# Segment16Keyboard.net
KiCad netlist of a schematic drawn in EAGLE
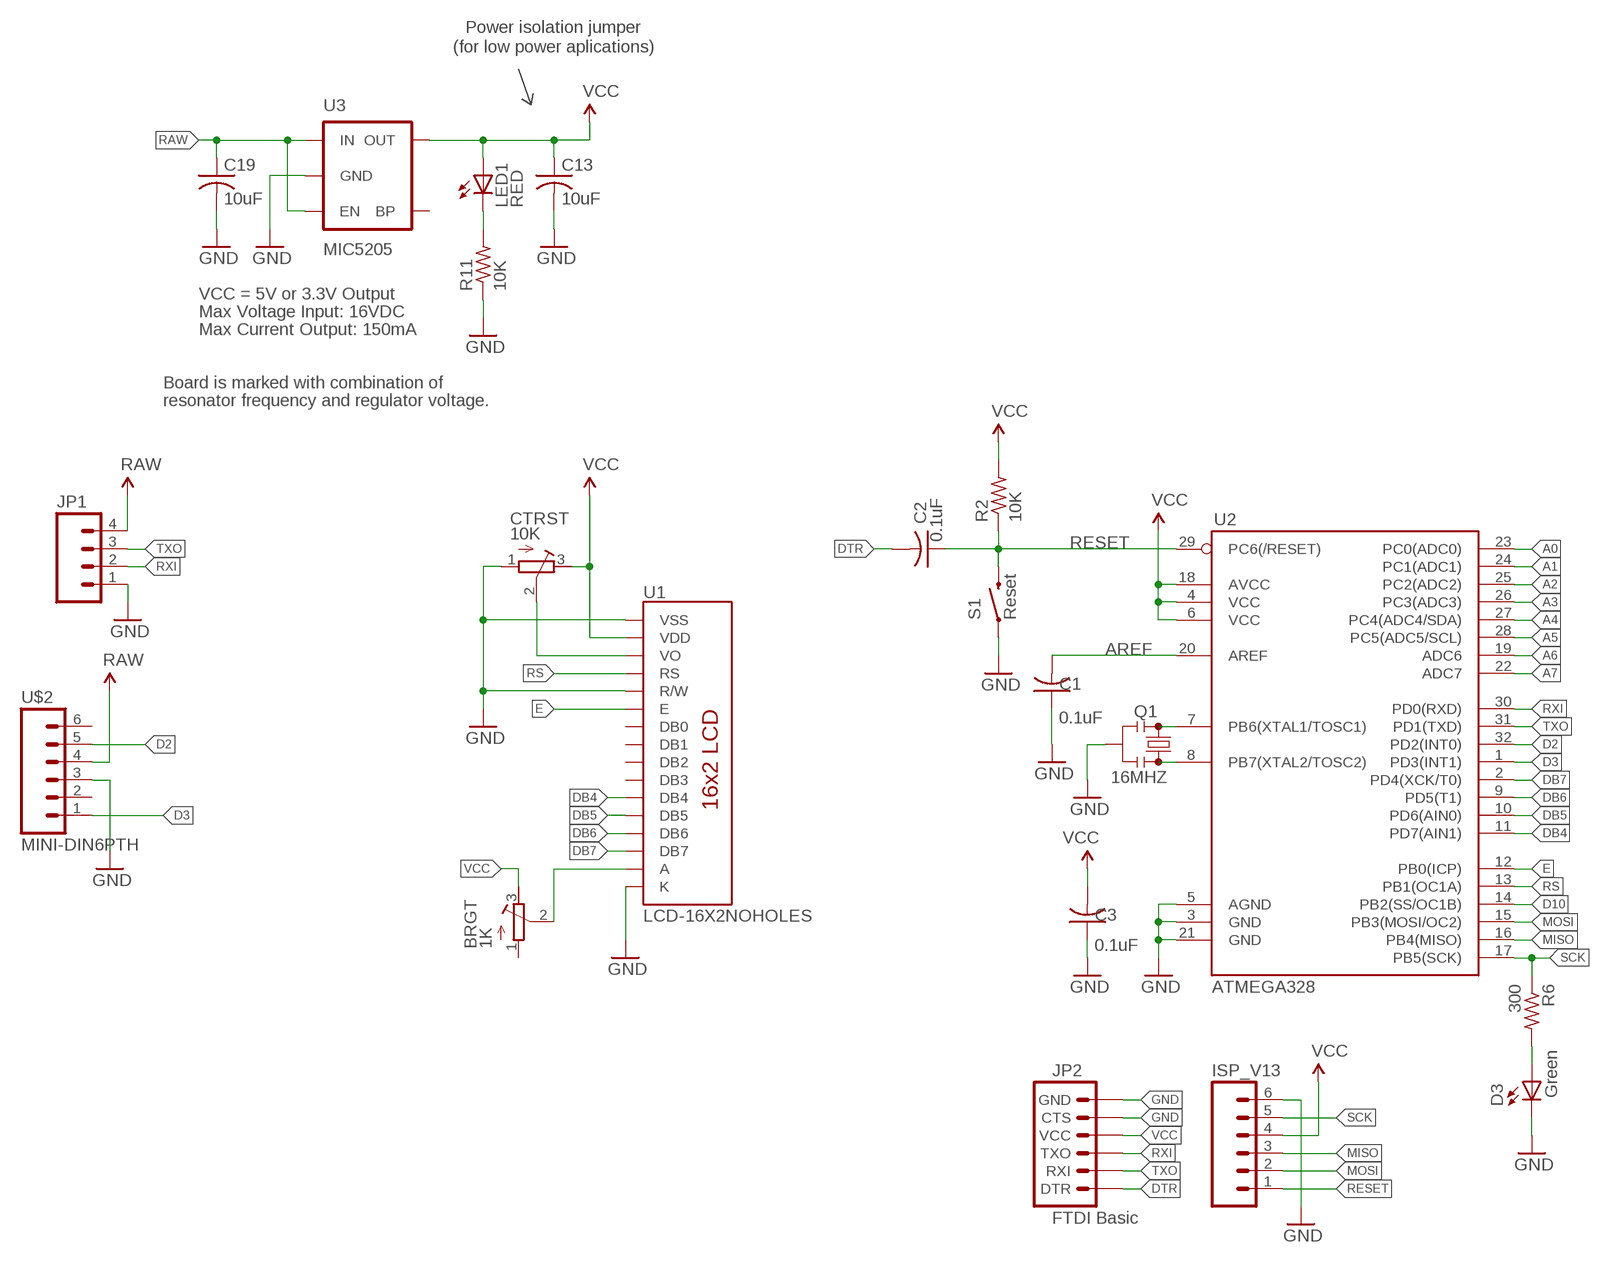
[diagram p0: schematic, sheet 1]

(export (version "E")
  (design (tool "Eeschema 10.0.6"))
  (components
    (comp (ref "BRGT")
      (value "1K")
      (footprint "eagle-import:RTRIM3296W")
      (libsource (lib "eagle-import") (part "R-TRIMM3296W"))
    )
    (comp (ref "C1")
      (value "0.1uF")
      (footprint "eagle-import:C0805")
      (libsource (lib "eagle-import") (part "C-USC0805"))
    )
    (comp (ref "C2")
      (value "0.1uF")
      (footprint "eagle-import:C0805")
      (libsource (lib "eagle-import") (part "C-USC0805"))
    )
    (comp (ref "C3")
      (value "0.1uF")
      (footprint "eagle-import:C0805")
      (libsource (lib "eagle-import") (part "C-USC0805"))
    )
    (comp (ref "C13")
      (value "10uF")
      (footprint "eagle-import:C0805")
      (libsource (lib "eagle-import") (part "resistor_C-USC0805"))
    )
    (comp (ref "C19")
      (value "10uF")
      (footprint "eagle-import:C0805")
      (libsource (lib "eagle-import") (part "resistor_C-USC0805"))
    )
    (comp (ref "CTRST")
      (value "10K")
      (footprint "eagle-import:RTRIM3296W")
      (libsource (lib "eagle-import") (part "R-TRIMM3296W"))
    )
    (comp (ref "D3")
      (value "Green")
      (footprint "eagle-import:CHIPLED_0805")
      (libsource (lib "eagle-import") (part "LEDCHIPLED_0805"))
    )
    (comp (ref "ISP_V13")
      (value "M06SIP")
      (footprint "eagle-import:1X06")
      (libsource (lib "eagle-import") (part "M06SIP"))
    )
    (comp (ref "JP1")
      (value "M041X04_NO_SILK")
      (footprint "eagle-import:1X04_NO_SILK")
      (libsource (lib "eagle-import") (part "M041X04_NO_SILK"))
    )
    (comp (ref "JP2")
      (value "FTDI Basic")
      (footprint "eagle-import:1X06")
      (libsource (lib "eagle-import") (part "ARDUINO_SERIAL_PROGRAMPTH"))
    )
    (comp (ref "LED1")
      (value "RED")
      (footprint "eagle-import:0603-LED-ALT1")
      (libsource (lib "eagle-import") (part "LED"))
    )
    (comp (ref "Q1")
      (value "16MHZ")
      (footprint "eagle-import:RESONATOR-SMD")
      (libsource (lib "eagle-import") (part "RESONATOR16MHZ"))
    )
    (comp (ref "R2")
      (value "10K")
      (footprint "eagle-import:M0805")
      (libsource (lib "eagle-import") (part "R-US_M0805"))
    )
    (comp (ref "R6")
      (value "300")
      (footprint "eagle-import:M0805")
      (libsource (lib "eagle-import") (part "R-US_M0805"))
    )
    (comp (ref "R11")
      (value "10K")
      (footprint "eagle-import:R0805")
      (libsource (lib "eagle-import") (part "R-US_R0805"))
    )
    (comp (ref "S1")
      (value "Reset")
      (footprint "eagle-import:TACTILE-SWITCH-SMD-ALT01")
      (libsource (lib "eagle-import") (part "SWITCH-MOMENTARY-2SMD-ALT01"))
    )
    (comp (ref "U$2")
      (value "MINI-DIN6PTH")
      (footprint "eagle-import:MINI-DIN6")
      (libsource (lib "eagle-import") (part "MINI-DIN6PTH"))
    )
    (comp (ref "U1")
      (value "LCD-16X2NOHOLES")
      (footprint "eagle-import:LCD-16X2_NOHOLES")
      (libsource (lib "eagle-import") (part "LCD-16X2NOHOLES"))
    )
    (comp (ref "U2")
      (value "ATMEGA328")
      (footprint "eagle-import:TQFP32-08")
      (libsource (lib "eagle-import") (part "ATMEGA168"))
    )
    (comp (ref "U3")
      (value "MIC5205")
      (footprint "eagle-import:SOT23-5")
      (libsource (lib "eagle-import") (part "V_REG_LDOSMD"))
    )
  )
  (nets
    (net (code "1") (name "/AREF") (class "Default")
      (node (ref "C1") (pin "2") (pinfunction "2_2") (pintype "passive"))
      (node (ref "U2") (pin "20") (pinfunction "AREF_20") (pintype "bidirectional"))
    )
    (net (code "2") (name "A0") (class "Default")
      (node (ref "U2") (pin "23") (pinfunction "PC0(ADC0)_23") (pintype "bidirectional"))
    )
    (net (code "3") (name "A1") (class "Default")
      (node (ref "U2") (pin "24") (pinfunction "PC1(ADC1)_24") (pintype "bidirectional"))
    )
    (net (code "4") (name "A2") (class "Default")
      (node (ref "U2") (pin "25") (pinfunction "PC2(ADC2)_25") (pintype "bidirectional"))
    )
    (net (code "5") (name "A3") (class "Default")
      (node (ref "U2") (pin "26") (pinfunction "PC3(ADC3)_26") (pintype "bidirectional"))
    )
    (net (code "6") (name "A4") (class "Default")
      (node (ref "U2") (pin "27") (pinfunction "PC4(ADC4/SDA)_27") (pintype "bidirectional"))
    )
    (net (code "7") (name "A5") (class "Default")
      (node (ref "U2") (pin "28") (pinfunction "PC5(ADC5/SCL)_28") (pintype "bidirectional"))
    )
    (net (code "8") (name "A6") (class "Default")
      (node (ref "U2") (pin "19") (pinfunction "ADC6_19") (pintype "bidirectional"))
    )
    (net (code "9") (name "A7") (class "Default")
      (node (ref "U2") (pin "22") (pinfunction "ADC7_22") (pintype "bidirectional"))
    )
    (net (code "10") (name "D2") (class "Default")
      (node (ref "U$2") (pin "5") (pinfunction "5_5") (pintype "passive"))
      (node (ref "U2") (pin "32") (pinfunction "PD2(INT0)_32") (pintype "bidirectional"))
    )
    (net (code "11") (name "D3") (class "Default")
      (node (ref "U$2") (pin "1") (pinfunction "1_1") (pintype "passive"))
      (node (ref "U2") (pin "1") (pinfunction "PD3(INT1)_1") (pintype "bidirectional"))
    )
    (net (code "12") (name "D10") (class "Default")
      (node (ref "U2") (pin "14") (pinfunction "PB2(SS/OC1B)_14") (pintype "bidirectional"))
    )
    (net (code "13") (name "DB4") (class "Default")
      (node (ref "U1") (pin "11") (pinfunction "DB4_11") (pintype "bidirectional"))
      (node (ref "U2") (pin "11") (pinfunction "PD7(AIN1)_11") (pintype "bidirectional"))
    )
    (net (code "14") (name "DB5") (class "Default")
      (node (ref "U1") (pin "12") (pinfunction "DB5_12") (pintype "bidirectional"))
      (node (ref "U2") (pin "10") (pinfunction "PD6(AIN0)_10") (pintype "bidirectional"))
    )
    (net (code "15") (name "DB6") (class "Default")
      (node (ref "U1") (pin "13") (pinfunction "DB6_13") (pintype "bidirectional"))
      (node (ref "U2") (pin "9") (pinfunction "PD5(T1)_9") (pintype "bidirectional"))
    )
    (net (code "16") (name "DB7") (class "Default")
      (node (ref "U1") (pin "14") (pinfunction "DB7_14") (pintype "bidirectional"))
      (node (ref "U2") (pin "2") (pinfunction "PD4(XCK/T0)_2") (pintype "bidirectional"))
    )
    (net (code "17") (name "DTR") (class "Default")
      (node (ref "C2") (pin "2") (pinfunction "2_2") (pintype "passive"))
      (node (ref "JP2") (pin "1") (pinfunction "DTR_1") (pintype "passive"))
    )
    (net (code "18") (name "E") (class "Default")
      (node (ref "U1") (pin "6") (pinfunction "E_6") (pintype "input"))
      (node (ref "U2") (pin "12") (pinfunction "PB0(ICP)_12") (pintype "bidirectional"))
    )
    (net (code "19") (name "GND") (class "Default")
      (node (ref "C1") (pin "1") (pinfunction "1_1") (pintype "passive"))
      (node (ref "C13") (pin "2") (pinfunction "2_2") (pintype "passive"))
      (node (ref "C19") (pin "2") (pinfunction "2_2") (pintype "passive"))
      (node (ref "C3") (pin "1") (pinfunction "1_1") (pintype "passive"))
      (node (ref "CTRST") (pin "1") (pinfunction "A_1") (pintype "passive"))
      (node (ref "D3") (pin "C") (pinfunction "C_C") (pintype "passive"))
      (node (ref "ISP_V13") (pin "6") (pinfunction "6_6") (pintype "passive"))
      (node (ref "JP1") (pin "1") (pinfunction "1_1") (pintype "passive"))
      (node (ref "JP2") (pin "5") (pinfunction "CTS_5") (pintype "passive"))
      (node (ref "JP2") (pin "6") (pinfunction "GND_6") (pintype "passive"))
      (node (ref "Q1") (pin "2") (pinfunction "2_2") (pintype "passive"))
      (node (ref "R11") (pin "1") (pinfunction "1_1") (pintype "passive"))
      (node (ref "S1") (pin "1") (pinfunction "1_1") (pintype "passive"))
      (node (ref "S1") (pin "2") (pinfunction "1_2") (pintype "passive"))
      (node (ref "U$2") (pin "3") (pinfunction "3_3") (pintype "passive"))
      (node (ref "U1") (pin "1") (pinfunction "VSS_1") (pintype "power_in"))
      (node (ref "U1") (pin "16") (pinfunction "K_16") (pintype "power_in"))
      (node (ref "U1") (pin "5") (pinfunction "R/W_5") (pintype "input"))
      (node (ref "U2") (pin "21") (pinfunction "GND_21") (pintype "bidirectional"))
      (node (ref "U2") (pin "3") (pinfunction "GND_3") (pintype "bidirectional"))
      (node (ref "U2") (pin "5") (pinfunction "AGND_5") (pintype "bidirectional"))
      (node (ref "U3") (pin "2") (pinfunction "GND_2") (pintype "input"))
    )
    (net (code "20") (name "MISO") (class "Default")
      (node (ref "ISP_V13") (pin "3") (pinfunction "3_3") (pintype "passive"))
      (node (ref "U2") (pin "16") (pinfunction "PB4(MISO)_16") (pintype "bidirectional"))
    )
    (net (code "21") (name "MOSI") (class "Default")
      (node (ref "ISP_V13") (pin "2") (pinfunction "2_2") (pintype "passive"))
      (node (ref "U2") (pin "15") (pinfunction "PB3(MOSI/OC2)_15") (pintype "bidirectional"))
    )
    (net (code "22") (name "Net-(BRGT-S)") (class "Default")
      (node (ref "BRGT") (pin "2") (pinfunction "S_2") (pintype "passive"))
      (node (ref "U1") (pin "15") (pinfunction "A_15") (pintype "power_in"))
    )
    (net (code "23") (name "Net-(CTRST-S)") (class "Default")
      (node (ref "CTRST") (pin "2") (pinfunction "S_2") (pintype "passive"))
      (node (ref "U1") (pin "3") (pinfunction "VO_3") (pintype "bidirectional"))
    )
    (net (code "24") (name "Net-(D3-PadA)") (class "Default")
      (node (ref "D3") (pin "A") (pinfunction "A_A") (pintype "passive"))
      (node (ref "R6") (pin "2") (pinfunction "2_2") (pintype "passive"))
    )
    (net (code "25") (name "Net-(LED1-PadC)") (class "Default")
      (node (ref "LED1") (pin "C") (pinfunction "C_C") (pintype "passive"))
      (node (ref "R11") (pin "2") (pinfunction "2_2") (pintype "passive"))
    )
    (net (code "26") (name "Net-(U2-PB6(XTAL1{slash}TOSC1))") (class "Default")
      (node (ref "Q1") (pin "1") (pinfunction "1_1") (pintype "passive"))
      (node (ref "U2") (pin "7") (pinfunction "PB6(XTAL1/TOSC1)_7") (pintype "bidirectional"))
    )
    (net (code "27") (name "Net-(U2-PB7(XTAL2{slash}TOSC2))") (class "Default")
      (node (ref "Q1") (pin "3") (pinfunction "3_3") (pintype "passive"))
      (node (ref "U2") (pin "8") (pinfunction "PB7(XTAL2/TOSC2)_8") (pintype "bidirectional"))
    )
    (net (code "28") (name "RAW") (class "Default")
      (node (ref "C19") (pin "1") (pinfunction "1_1") (pintype "passive"))
      (node (ref "JP1") (pin "4") (pinfunction "4_4") (pintype "passive"))
      (node (ref "U$2") (pin "4") (pinfunction "4_4") (pintype "passive"))
      (node (ref "U3") (pin "1") (pinfunction "IN_1") (pintype "input"))
      (node (ref "U3") (pin "3") (pinfunction "EN_3") (pintype "input"))
    )
    (net (code "29") (name "RESET") (class "Default")
      (node (ref "C2") (pin "1") (pinfunction "1_1") (pintype "passive"))
      (node (ref "ISP_V13") (pin "1") (pinfunction "1_1") (pintype "passive"))
      (node (ref "R2") (pin "1") (pinfunction "1_1") (pintype "passive"))
      (node (ref "S1") (pin "3") (pinfunction "2_3") (pintype "passive"))
      (node (ref "S1") (pin "4") (pinfunction "2_4") (pintype "passive"))
      (node (ref "U2") (pin "29") (pinfunction "PC6(/RESET)_29") (pintype "bidirectional"))
    )
    (net (code "30") (name "RS") (class "Default")
      (node (ref "U1") (pin "4") (pinfunction "RS_4") (pintype "input"))
      (node (ref "U2") (pin "13") (pinfunction "PB1(OC1A)_13") (pintype "bidirectional"))
    )
    (net (code "31") (name "RXI") (class "Default")
      (node (ref "JP1") (pin "2") (pinfunction "2_2") (pintype "passive"))
      (node (ref "JP2") (pin "3") (pinfunction "TXO_3") (pintype "passive"))
      (node (ref "U2") (pin "30") (pinfunction "PD0(RXD)_30") (pintype "bidirectional"))
    )
    (net (code "32") (name "SCK") (class "Default")
      (node (ref "ISP_V13") (pin "5") (pinfunction "5_5") (pintype "passive"))
      (node (ref "R6") (pin "1") (pinfunction "1_1") (pintype "passive"))
      (node (ref "U2") (pin "17") (pinfunction "PB5(SCK)_17") (pintype "bidirectional"))
    )
    (net (code "33") (name "TXO") (class "Default")
      (node (ref "JP1") (pin "3") (pinfunction "3_3") (pintype "passive"))
      (node (ref "JP2") (pin "2") (pinfunction "RXI_2") (pintype "passive"))
      (node (ref "U2") (pin "31") (pinfunction "PD1(TXD)_31") (pintype "bidirectional"))
    )
    (net (code "34") (name "VCC") (class "Default")
      (node (ref "BRGT") (pin "3") (pinfunction "E_3") (pintype "passive"))
      (node (ref "C13") (pin "1") (pinfunction "1_1") (pintype "passive"))
      (node (ref "C3") (pin "2") (pinfunction "2_2") (pintype "passive"))
      (node (ref "CTRST") (pin "3") (pinfunction "E_3") (pintype "passive"))
      (node (ref "ISP_V13") (pin "4") (pinfunction "4_4") (pintype "passive"))
      (node (ref "JP2") (pin "4") (pinfunction "VCC_4") (pintype "passive"))
      (node (ref "LED1") (pin "A") (pinfunction "A_A") (pintype "passive"))
      (node (ref "R2") (pin "2") (pinfunction "2_2") (pintype "passive"))
      (node (ref "U1") (pin "2") (pinfunction "VDD_2") (pintype "power_in"))
      (node (ref "U2") (pin "18") (pinfunction "AVCC_18") (pintype "bidirectional"))
      (node (ref "U2") (pin "4") (pinfunction "VCC_4") (pintype "bidirectional"))
      (node (ref "U2") (pin "6") (pinfunction "VCC_6") (pintype "bidirectional"))
      (node (ref "U3") (pin "5") (pinfunction "OUT_5") (pintype "passive"))
    )
    (net (code "35") (name "unconnected-(BRGT-A-Pad1)") (class "Default")
      (node (ref "BRGT") (pin "1") (pinfunction "A_1") (pintype "passive"))
    )
    (net (code "36") (name "unconnected-(U$2-Pad2)") (class "Default")
      (node (ref "U$2") (pin "2") (pinfunction "2_2") (pintype "passive"))
    )
    (net (code "37") (name "unconnected-(U$2-Pad6)") (class "Default")
      (node (ref "U$2") (pin "6") (pinfunction "6_6") (pintype "passive"))
    )
    (net (code "38") (name "unconnected-(U1-DB0-Pad7)") (class "Default")
      (node (ref "U1") (pin "7") (pinfunction "DB0_7") (pintype "bidirectional"))
    )
    (net (code "39") (name "unconnected-(U1-DB1-Pad8)") (class "Default")
      (node (ref "U1") (pin "8") (pinfunction "DB1_8") (pintype "bidirectional"))
    )
    (net (code "40") (name "unconnected-(U1-DB2-Pad9)") (class "Default")
      (node (ref "U1") (pin "9") (pinfunction "DB2_9") (pintype "bidirectional"))
    )
    (net (code "41") (name "unconnected-(U1-DB3-Pad10)") (class "Default")
      (node (ref "U1") (pin "10") (pinfunction "DB3_10") (pintype "bidirectional"))
    )
    (net (code "42") (name "unconnected-(U3-BP-Pad4)") (class "Default")
      (node (ref "U3") (pin "4") (pinfunction "BP_4") (pintype "input"))
    )
  )
)
